# BTL_DLCN.net
KiCad netlist of a schematic drawn in Altium Designer
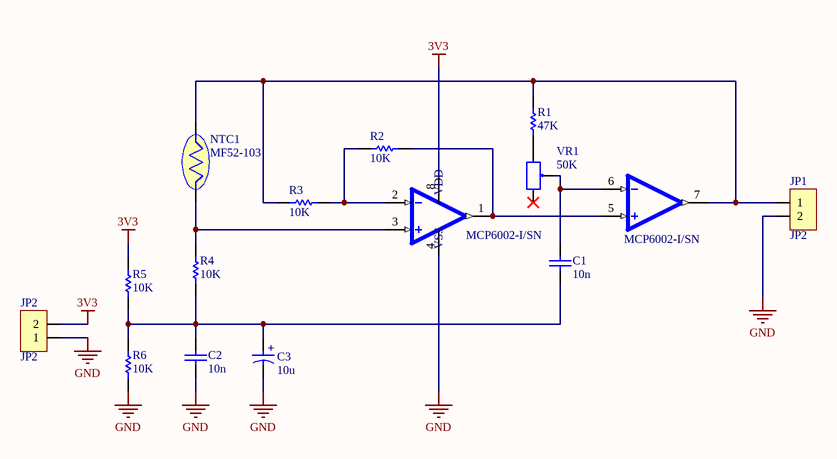
[diagram p0: BTL_DLCN.SchDoc]

(export (version "E")
  (design (tool "Eeschema 10.0.6"))
  (components
    (comp (ref "C1")
      (value "10n")
      (footprint "CAP_0805")
      (description "CAP, size 0805, 2.7 uF, 50 VDC")
      (fields (field (name "TOLERANCE") "+/-5%"))
      (libsource (lib "Altium_Ceramic_Cap") (part "0108052781050"))
    )
    (comp (ref "C2")
      (value "10n")
      (footprint "CAP_0805")
      (description "CAP, size 0805, 2.7 uF, 50 VDC")
      (fields (field (name "TOLERANCE") "+/-5%"))
      (libsource (lib "Altium_Ceramic_Cap") (part "0108052781050"))
    )
    (comp (ref "C3")
      (value "10u")
      (footprint "WCAP-ASLI_D5H5.5")
      (description "V-Chip, D5 x H5.5mm, 100uF, 6.3V")
      (fields (field (name "MANUFACTURER") "Wurth Elektronik"))
      (libsource (lib "Altium_Alutinum_Cap") (part "865080142007"))
    )
    (comp (ref "JP1")
      (value "JP2")
      (footprint "JP2-D1T")
      (description "WR-PHD 2.54 mm Angled Socket Header")
      (fields
        (field (name "MANUFACTURER") "Würth Elektronik eiSos GmbH")
        (field (name "PARTNO") "613002143121")
        (field (name "CREATED BY") "Karrer Zheng")
      )
      (libsource (lib "KhanhBK_Library_4") (part "JP2"))
    )
    (comp (ref "JP2")
      (value "JP2")
      (footprint "JP2-D1T")
      (description "WR-PHD 2.54 mm Angled Socket Header")
      (fields
        (field (name "MANUFACTURER") "Würth Elektronik eiSos GmbH")
        (field (name "PARTNO") "613002143121")
        (field (name "CREATED BY") "Karrer Zheng")
      )
      (libsource (lib "") (part "JP2_1"))
    )
    (comp (ref "NTC1") (value "MF52-103") (footprint "NTC10D") (libsource (lib "Cty1") (part "NTC10D")))
    (comp (ref "R1")
      (value "47K")
      (footprint "RESISTOR_0805")
      (description "https://www.thegioiic.com/dien-tro-47-kohm-0805-1-")
      (libsource (lib "Altium_Resistor") (part "0008054755"))
    )
    (comp (ref "R2")
      (value "10K")
      (footprint "RESISTOR_0805")
      (description "RES, size 0805, 4.7 MOhm, 1/8W")
      (libsource (lib "Altium_Resistor") (part "0008054755"))
    )
    (comp (ref "R3")
      (value "10K")
      (footprint "RESISTOR_0805")
      (description "https://www.thegioiic.com/dien-tro-10-kohm-0805-1-")
      (libsource (lib "Altium_Resistor") (part "0008054755"))
    )
    (comp (ref "R4")
      (value "10K")
      (footprint "RESISTOR_0805")
      (description "https://www.thegioiic.com/dien-tro-10-kohm-0805-1-")
      (libsource (lib "Altium_Resistor") (part "0008054755"))
    )
    (comp (ref "R5")
      (value "10K")
      (footprint "RESISTOR_0805")
      (description "RES, size 0805, 4.7 MOhm, 1/8W")
      (libsource (lib "Altium_Resistor") (part "0008054755"))
    )
    (comp (ref "R6")
      (value "10K")
      (footprint "RESISTOR_0805")
      (description "RES, size 0805, 4.7 MOhm, 1/8W")
      (libsource (lib "Altium_Resistor") (part "0008054755"))
    )
    (comp (ref "U1")
      (value "MCP6002-I/SN")
      (footprint "SOIC127P600X175-8N")
      (fields (field (name "MF") "Microchip"))
      (libsource (lib "MCP6002-I_SN") (part "MCP6002-I/SN"))
    )
    (comp (ref "VR1")
      (value "50K")
      (footprint "VR-S3")
      (description "https://www.thegioiic.com/3296w-503-bien-tro-chiet-ap-50-kohm-3-chan-chinh-top-0-5w")
      (libsource (lib "KhanhBK_Library_4") (part "Resistor Var"))
    )
  )
  (nets
    (net (code "1") (name "3V3") (class "Default")
      (node (ref "JP2") (pin "2") (pinfunction "2_2") (pintype "passive"))
      (node (ref "R5") (pin "1") (pinfunction "1_1") (pintype "passive"))
      (node (ref "U1") (pin "8") (pinfunction "VDD_8") (pintype "power_in"))
    )
    (net (code "2") (name "GND") (class "Default")
      (node (ref "C2") (pin "1") (pinfunction "1_1") (pintype "passive"))
      (node (ref "C3") (pin "2") (pinfunction "N_2") (pintype "passive"))
      (node (ref "JP1") (pin "2") (pinfunction "2_2") (pintype "passive"))
      (node (ref "JP2") (pin "1") (pinfunction "1_1") (pintype "passive"))
      (node (ref "R6") (pin "2") (pinfunction "2_2") (pintype "passive"))
      (node (ref "U1") (pin "4") (pinfunction "VSS_4") (pintype "power_in"))
    )
    (net (code "3") (name "Net-(C3-P)") (class "Default")
      (node (ref "C1") (pin "1") (pinfunction "1_1") (pintype "passive"))
      (node (ref "C2") (pin "2") (pinfunction "2_2") (pintype "passive"))
      (node (ref "C3") (pin "1") (pinfunction "P_1") (pintype "passive"))
      (node (ref "R4") (pin "2") (pinfunction "2_2") (pintype "passive"))
      (node (ref "R5") (pin "2") (pinfunction "2_2") (pintype "passive"))
      (node (ref "R6") (pin "1") (pinfunction "1_1") (pintype "passive"))
    )
    (net (code "4") (name "Net-(R1-Pad1)") (class "Default")
      (node (ref "R1") (pin "1") (pinfunction "1_1") (pintype "passive"))
      (node (ref "VR1") (pin "1") (pinfunction "1_1") (pintype "passive"))
    )
    (net (code "5") (name "Net-(U1A-VINA+)") (class "Default")
      (node (ref "NTC1") (pin "1") (pinfunction "1_1") (pintype "passive"))
      (node (ref "R4") (pin "1") (pinfunction "1_1") (pintype "passive"))
      (node (ref "U1") (pin "3") (pinfunction "VINA+_3") (pintype "input"))
    )
    (net (code "6") (name "Net-(U1A-VINA-)") (class "Default")
      (node (ref "R2") (pin "2") (pinfunction "2_2") (pintype "passive"))
      (node (ref "R3") (pin "1") (pinfunction "1_1") (pintype "passive"))
      (node (ref "U1") (pin "2") (pinfunction "VINA-_2") (pintype "input"))
    )
    (net (code "7") (name "Net-(U1A-VOUTA)") (class "Default")
      (node (ref "R2") (pin "1") (pinfunction "1_1") (pintype "passive"))
      (node (ref "U1") (pin "1") (pinfunction "VOUTA_1") (pintype "output"))
      (node (ref "U1") (pin "5") (pinfunction "VINB+_5") (pintype "input"))
    )
    (net (code "8") (name "Net-(U1B-VINB-)") (class "Default")
      (node (ref "C1") (pin "2") (pinfunction "2_2") (pintype "passive"))
      (node (ref "U1") (pin "6") (pinfunction "VINB-_6") (pintype "input"))
      (node (ref "VR1") (pin "2") (pinfunction "2_2") (pintype "passive"))
    )
    (net (code "9") (name "Net-(U1B-VOUTB)") (class "Default")
      (node (ref "JP1") (pin "1") (pinfunction "1_1") (pintype "passive"))
      (node (ref "NTC1") (pin "2") (pinfunction "2_2") (pintype "passive"))
      (node (ref "R1") (pin "2") (pinfunction "2_2") (pintype "passive"))
      (node (ref "R3") (pin "2") (pinfunction "2_2") (pintype "passive"))
      (node (ref "U1") (pin "7") (pinfunction "VOUTB_7") (pintype "output"))
    )
    (net (code "10") (name "unconnected-(VR1-Pad3)") (class "Default")
      (node (ref "VR1") (pin "3") (pinfunction "3_3") (pintype "passive+no_connect"))
    )
  )
)
